# Sheet2.net
KiCad netlist of a schematic drawn in Altium Designer
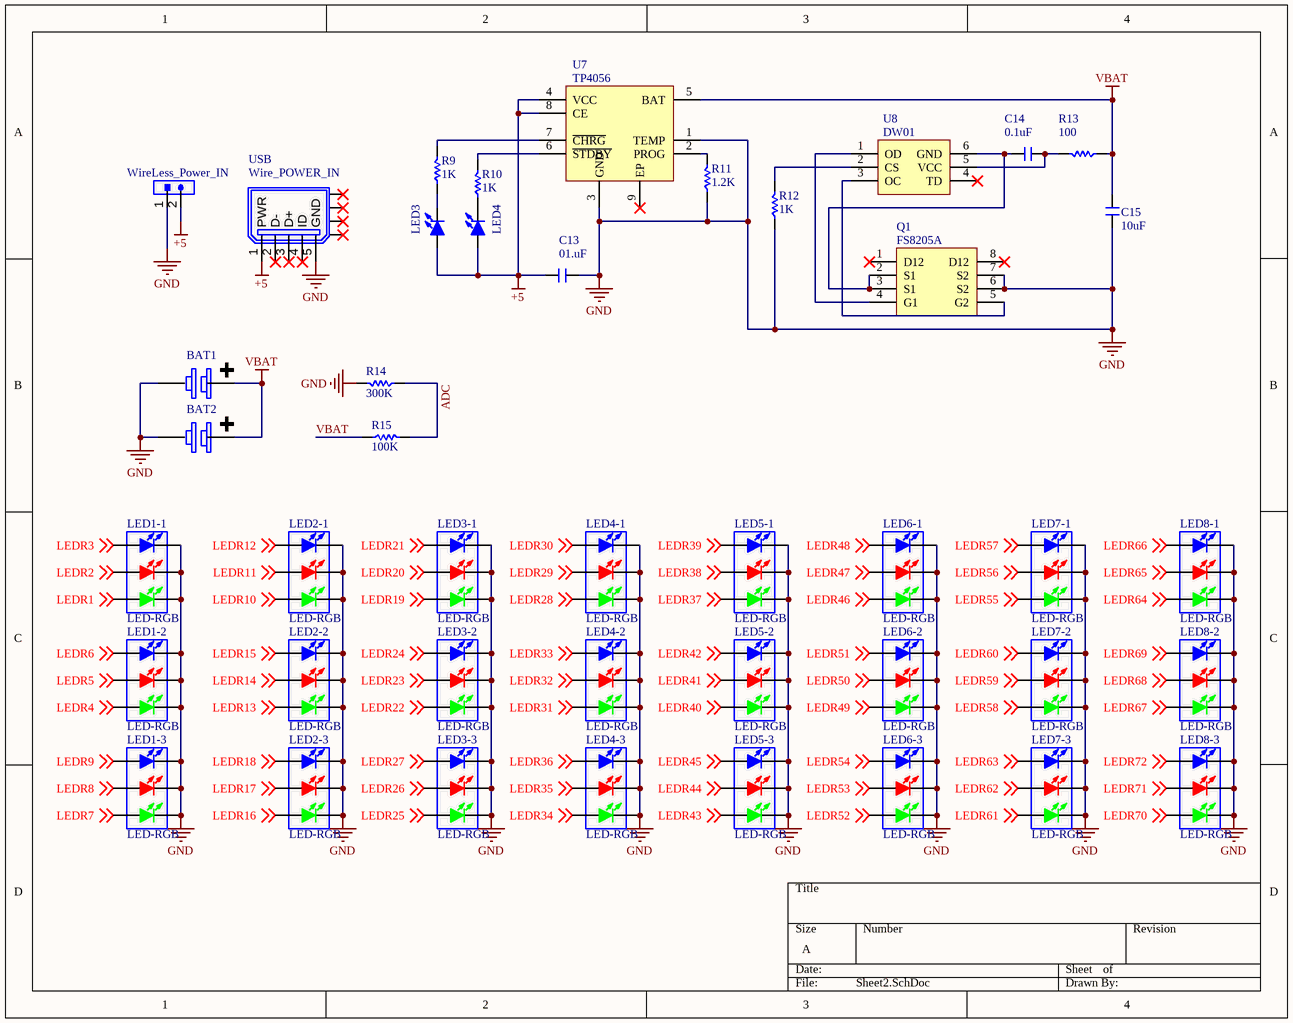
[diagram p0: Sheet2.SchDoc]

(export (version "E")
  (design (tool "Eeschema 10.0.6"))
  (components
    (comp (ref "BAT1")
      (value "Battery 1850")
      (footprint "18650 Single")
      (libsource (lib "Battery Holder") (part "Battery 1850"))
    )
    (comp (ref "BAT2")
      (value "Battery 1850")
      (footprint "18650 Single")
      (libsource (lib "Battery Holder") (part "Battery 1850"))
    )
    (comp (ref "C13")
      (value "01.uF")
      (footprint "C 0402")
      (description "Non-polar patch capacitor")
      (fields (field (name "版权归属") "源创客"))
      (libsource (lib "Passive (Resistor-Capacitor-Inductor-Veristor-Ferrite)") (part "C"))
    )
    (comp (ref "C14")
      (value "0.1uF")
      (footprint "C 0402")
      (description "Non-polar patch capacitor")
      (fields (field (name "版权归属") "源创客"))
      (libsource (lib "Passive (Resistor-Capacitor-Inductor-Veristor-Ferrite)") (part "C"))
    )
    (comp (ref "C15")
      (value "10uF")
      (footprint "C 0603")
      (description "Non-polar patch capacitor")
      (fields (field (name "版权归属") "源创客"))
      (libsource (lib "Passive (Resistor-Capacitor-Inductor-Veristor-Ferrite)") (part "C"))
    )
    (comp (ref "LED1-1")
      (value "LED-RGB")
      (footprint "LED 5050")
      (description "Three primary color LED")
      (fields (field (name "版权归属") "源创客"))
      (libsource (lib "LED") (part "LED-RGB"))
    )
    (comp (ref "LED1-2")
      (value "LED-RGB")
      (footprint "LED 5050")
      (description "Three primary color LED")
      (fields (field (name "版权归属") "源创客"))
      (libsource (lib "LED") (part "LED-RGB"))
    )
    (comp (ref "LED1-3")
      (value "LED-RGB")
      (footprint "LED 5050")
      (description "Three primary color LED")
      (fields (field (name "版权归属") "源创客"))
      (libsource (lib "LED") (part "LED-RGB"))
    )
    (comp (ref "LED2-1")
      (value "LED-RGB")
      (footprint "LED 5050")
      (description "Three primary color LED")
      (fields (field (name "版权归属") "源创客"))
      (libsource (lib "LED") (part "LED-RGB"))
    )
    (comp (ref "LED2-2")
      (value "LED-RGB")
      (footprint "LED 5050")
      (description "Three primary color LED")
      (fields (field (name "版权归属") "源创客"))
      (libsource (lib "LED") (part "LED-RGB"))
    )
    (comp (ref "LED2-3")
      (value "LED-RGB")
      (footprint "LED 5050")
      (description "Three primary color LED")
      (fields (field (name "版权归属") "源创客"))
      (libsource (lib "LED") (part "LED-RGB"))
    )
    (comp (ref "LED3")
      (value "LED-SMD")
      (footprint "LED 0805R")
      (description "Patch LED")
      (fields (field (name "版权归属") "源创客"))
      (libsource (lib "LED") (part "LED-SMD"))
    )
    (comp (ref "LED3-1")
      (value "LED-RGB")
      (footprint "LED 5050")
      (description "Three primary color LED")
      (fields (field (name "版权归属") "源创客"))
      (libsource (lib "LED") (part "LED-RGB"))
    )
    (comp (ref "LED3-2")
      (value "LED-RGB")
      (footprint "LED 5050")
      (description "Three primary color LED")
      (fields (field (name "版权归属") "源创客"))
      (libsource (lib "LED") (part "LED-RGB"))
    )
    (comp (ref "LED3-3")
      (value "LED-RGB")
      (footprint "LED 5050")
      (description "Three primary color LED")
      (fields (field (name "版权归属") "源创客"))
      (libsource (lib "LED") (part "LED-RGB"))
    )
    (comp (ref "LED4")
      (value "LED-SMD")
      (footprint "LED 0805G")
      (description "Patch LED")
      (fields (field (name "版权归属") "源创客"))
      (libsource (lib "LED") (part "LED-SMD"))
    )
    (comp (ref "LED4-1")
      (value "LED-RGB")
      (footprint "LED 5050")
      (description "Three primary color LED")
      (fields (field (name "版权归属") "源创客"))
      (libsource (lib "LED") (part "LED-RGB"))
    )
    (comp (ref "LED4-2")
      (value "LED-RGB")
      (footprint "LED 5050")
      (description "Three primary color LED")
      (fields (field (name "版权归属") "源创客"))
      (libsource (lib "LED") (part "LED-RGB"))
    )
    (comp (ref "LED4-3")
      (value "LED-RGB")
      (footprint "LED 5050")
      (description "Three primary color LED")
      (fields (field (name "版权归属") "源创客"))
      (libsource (lib "LED") (part "LED-RGB"))
    )
    (comp (ref "LED5-1")
      (value "LED-RGB")
      (footprint "LED 5050")
      (description "Three primary color LED")
      (fields (field (name "版权归属") "源创客"))
      (libsource (lib "LED") (part "LED-RGB"))
    )
    (comp (ref "LED5-2")
      (value "LED-RGB")
      (footprint "LED 5050")
      (description "Three primary color LED")
      (fields (field (name "版权归属") "源创客"))
      (libsource (lib "LED") (part "LED-RGB"))
    )
    (comp (ref "LED5-3")
      (value "LED-RGB")
      (footprint "LED 5050")
      (description "Three primary color LED")
      (fields (field (name "版权归属") "源创客"))
      (libsource (lib "LED") (part "LED-RGB"))
    )
    (comp (ref "LED6-1")
      (value "LED-RGB")
      (footprint "LED 5050")
      (description "Three primary color LED")
      (fields (field (name "版权归属") "源创客"))
      (libsource (lib "LED") (part "LED-RGB"))
    )
    (comp (ref "LED6-2")
      (value "LED-RGB")
      (footprint "LED 5050")
      (description "Three primary color LED")
      (fields (field (name "版权归属") "源创客"))
      (libsource (lib "LED") (part "LED-RGB"))
    )
    (comp (ref "LED6-3")
      (value "LED-RGB")
      (footprint "LED 5050")
      (description "Three primary color LED")
      (fields (field (name "版权归属") "源创客"))
      (libsource (lib "LED") (part "LED-RGB"))
    )
    (comp (ref "LED7-1")
      (value "LED-RGB")
      (footprint "LED 5050")
      (description "Three primary color LED")
      (fields (field (name "版权归属") "源创客"))
      (libsource (lib "LED") (part "LED-RGB"))
    )
    (comp (ref "LED7-2")
      (value "LED-RGB")
      (footprint "LED 5050")
      (description "Three primary color LED")
      (fields (field (name "版权归属") "源创客"))
      (libsource (lib "LED") (part "LED-RGB"))
    )
    (comp (ref "LED7-3")
      (value "LED-RGB")
      (footprint "LED 5050")
      (description "Three primary color LED")
      (fields (field (name "版权归属") "源创客"))
      (libsource (lib "LED") (part "LED-RGB"))
    )
    (comp (ref "LED8-1")
      (value "LED-RGB")
      (footprint "LED 5050")
      (description "Three primary color LED")
      (fields (field (name "版权归属") "源创客"))
      (libsource (lib "LED") (part "LED-RGB"))
    )
    (comp (ref "LED8-2")
      (value "LED-RGB")
      (footprint "LED 5050")
      (description "Three primary color LED")
      (fields (field (name "版权归属") "源创客"))
      (libsource (lib "LED") (part "LED-RGB"))
    )
    (comp (ref "LED8-3")
      (value "LED-RGB")
      (footprint "LED 5050")
      (description "Three primary color LED")
      (fields (field (name "版权归属") "源创客"))
      (libsource (lib "LED") (part "LED-RGB"))
    )
    (comp (ref "Q1")
      (value "FS8205A")
      (footprint "SSOP8_L")
      (description "Dual N-Channel Enhancement Mode Power MOSFET")
      (libsource (lib "Integrated Circuit") (part "FS8205A"))
    )
    (comp (ref "R9")
      (value "1K")
      (footprint "R 0402")
      (description "Chip resistor")
      (fields (field (name "版权归属") "源创客"))
      (libsource (lib "Passive (Resistor-Capacitor-Inductor-Veristor-Ferrite)") (part "R"))
    )
    (comp (ref "R10")
      (value "1K")
      (footprint "R 0402")
      (description "Chip resistor")
      (fields (field (name "版权归属") "源创客"))
      (libsource (lib "Passive (Resistor-Capacitor-Inductor-Veristor-Ferrite)") (part "R"))
    )
    (comp (ref "R11")
      (value "1.2K")
      (footprint "R 0402")
      (description "Chip resistor")
      (fields (field (name "版权归属") "源创客"))
      (libsource (lib "Passive (Resistor-Capacitor-Inductor-Veristor-Ferrite)") (part "R"))
    )
    (comp (ref "R12")
      (value "1K")
      (footprint "R 0402")
      (description "Chip resistor")
      (fields (field (name "版权归属") "源创客"))
      (libsource (lib "Passive (Resistor-Capacitor-Inductor-Veristor-Ferrite)") (part "R"))
    )
    (comp (ref "R13")
      (value "100")
      (footprint "R 0402")
      (description "Chip resistor")
      (fields (field (name "版权归属") "源创客"))
      (libsource (lib "Passive (Resistor-Capacitor-Inductor-Veristor-Ferrite)") (part "R"))
    )
    (comp (ref "R14")
      (value "300K")
      (footprint "R 0805")
      (description "Chip resistor")
      (fields (field (name "版权归属") "源创客"))
      (libsource (lib "Passive (Resistor-Capacitor-Inductor-Veristor-Ferrite)") (part "R"))
    )
    (comp (ref "R15")
      (value "100K")
      (footprint "R 0805")
      (description "Chip resistor")
      (fields (field (name "版权归属") "源创客"))
      (libsource (lib "Passive (Resistor-Capacitor-Inductor-Veristor-Ferrite)") (part "R"))
    )
    (comp (ref "U7")
      (value "TP4056")
      (footprint "SOP8_M-EP")
      (description "Lithium battery charge management")
      (fields (field (name "版权归属") "源创客"))
      (libsource (lib "Integrated Circuit") (part "TP4056"))
    )
    (comp (ref "U8")
      (value "DW01")
      (footprint "SOT23-6M")
      (description "Lithium battery overcurrent protection IC")
      (fields (field (name "版权归属") "源创客"))
      (libsource (lib "Integrated Circuit") (part "DW01"))
    )
    (comp (ref "USB")
      (value "Wire_POWER_IN")
      (footprint "USB-micro_B")
      (description "Micro & Mini USB female")
      (fields (field (name "版权归属") "源创客"))
      (libsource (lib "IO (Power-USB-Serial-VGA-RJ-Audio-Buzzer)") (part "USB-5P"))
    )
    (comp (ref "WireLess_Power_IN")
      (value "HDR-1X2")
      (footprint "XH2.54-2P")
      (description "2P Connector")
      (fields (field (name "版权归属") "源创客"))
      (libsource (lib "Connectors") (part "Header 2"))
    )
  )
  (nets
    (net (code "1") (name "+5") (class "Default")
      (node (ref "C13") (pin "2") (pinfunction "2_2") (pintype "passive"))
      (node (ref "LED3") (pin "1") (pinfunction "A_1") (pintype "passive"))
      (node (ref "LED4") (pin "1") (pinfunction "A_1") (pintype "passive"))
      (node (ref "U7") (pin "4") (pinfunction "VCC_4") (pintype "passive"))
      (node (ref "U7") (pin "8") (pinfunction "CE_8") (pintype "passive"))
      (node (ref "USB") (pin "1") (pinfunction "PWR_1") (pintype "power_in"))
      (node (ref "WireLess_Power_IN") (pin "2") (pintype "passive"))
    )
    (net (code "2") (name "/ADC") (class "Default")
      (node (ref "R14") (pin "1") (pinfunction "1_1") (pintype "passive"))
      (node (ref "R15") (pin "2") (pinfunction "2_2") (pintype "passive"))
    )
    (net (code "3") (name "GND") (class "Default")
      (node (ref "BAT1") (pin "2") (pinfunction "-_2") (pintype "passive"))
      (node (ref "BAT2") (pin "2") (pinfunction "-_2") (pintype "passive"))
      (node (ref "C13") (pin "1") (pinfunction "1_1") (pintype "passive"))
      (node (ref "C15") (pin "1") (pinfunction "1_1") (pintype "passive"))
      (node (ref "LED1-1") (pin "2") (pinfunction "BULE_K_2") (pintype "passive"))
      (node (ref "LED1-1") (pin "4") (pinfunction "RED_K_4") (pintype "passive"))
      (node (ref "LED1-1") (pin "6") (pinfunction "GREEN_K_6") (pintype "passive"))
      (node (ref "LED1-2") (pin "2") (pinfunction "BULE_K_2") (pintype "passive"))
      (node (ref "LED1-2") (pin "4") (pinfunction "RED_K_4") (pintype "passive"))
      (node (ref "LED1-2") (pin "6") (pinfunction "GREEN_K_6") (pintype "passive"))
      (node (ref "LED1-3") (pin "2") (pinfunction "BULE_K_2") (pintype "passive"))
      (node (ref "LED1-3") (pin "4") (pinfunction "RED_K_4") (pintype "passive"))
      (node (ref "LED1-3") (pin "6") (pinfunction "GREEN_K_6") (pintype "passive"))
      (node (ref "LED2-1") (pin "2") (pinfunction "BULE_K_2") (pintype "passive"))
      (node (ref "LED2-1") (pin "4") (pinfunction "RED_K_4") (pintype "passive"))
      (node (ref "LED2-1") (pin "6") (pinfunction "GREEN_K_6") (pintype "passive"))
      (node (ref "LED2-2") (pin "2") (pinfunction "BULE_K_2") (pintype "passive"))
      (node (ref "LED2-2") (pin "4") (pinfunction "RED_K_4") (pintype "passive"))
      (node (ref "LED2-2") (pin "6") (pinfunction "GREEN_K_6") (pintype "passive"))
      (node (ref "LED2-3") (pin "2") (pinfunction "BULE_K_2") (pintype "passive"))
      (node (ref "LED2-3") (pin "4") (pinfunction "RED_K_4") (pintype "passive"))
      (node (ref "LED2-3") (pin "6") (pinfunction "GREEN_K_6") (pintype "passive"))
      (node (ref "LED3-1") (pin "2") (pinfunction "BULE_K_2") (pintype "passive"))
      (node (ref "LED3-1") (pin "4") (pinfunction "RED_K_4") (pintype "passive"))
      (node (ref "LED3-1") (pin "6") (pinfunction "GREEN_K_6") (pintype "passive"))
      (node (ref "LED3-2") (pin "2") (pinfunction "BULE_K_2") (pintype "passive"))
      (node (ref "LED3-2") (pin "4") (pinfunction "RED_K_4") (pintype "passive"))
      (node (ref "LED3-2") (pin "6") (pinfunction "GREEN_K_6") (pintype "passive"))
      (node (ref "LED3-3") (pin "2") (pinfunction "BULE_K_2") (pintype "passive"))
      (node (ref "LED3-3") (pin "4") (pinfunction "RED_K_4") (pintype "passive"))
      (node (ref "LED3-3") (pin "6") (pinfunction "GREEN_K_6") (pintype "passive"))
      (node (ref "LED4-1") (pin "2") (pinfunction "BULE_K_2") (pintype "passive"))
      (node (ref "LED4-1") (pin "4") (pinfunction "RED_K_4") (pintype "passive"))
      (node (ref "LED4-1") (pin "6") (pinfunction "GREEN_K_6") (pintype "passive"))
      (node (ref "LED4-2") (pin "2") (pinfunction "BULE_K_2") (pintype "passive"))
      (node (ref "LED4-2") (pin "4") (pinfunction "RED_K_4") (pintype "passive"))
      (node (ref "LED4-2") (pin "6") (pinfunction "GREEN_K_6") (pintype "passive"))
      (node (ref "LED4-3") (pin "2") (pinfunction "BULE_K_2") (pintype "passive"))
      (node (ref "LED4-3") (pin "4") (pinfunction "RED_K_4") (pintype "passive"))
      (node (ref "LED4-3") (pin "6") (pinfunction "GREEN_K_6") (pintype "passive"))
      (node (ref "LED5-1") (pin "2") (pinfunction "BULE_K_2") (pintype "passive"))
      (node (ref "LED5-1") (pin "4") (pinfunction "RED_K_4") (pintype "passive"))
      (node (ref "LED5-1") (pin "6") (pinfunction "GREEN_K_6") (pintype "passive"))
      (node (ref "LED5-2") (pin "2") (pinfunction "BULE_K_2") (pintype "passive"))
      (node (ref "LED5-2") (pin "4") (pinfunction "RED_K_4") (pintype "passive"))
      (node (ref "LED5-2") (pin "6") (pinfunction "GREEN_K_6") (pintype "passive"))
      (node (ref "LED5-3") (pin "2") (pinfunction "BULE_K_2") (pintype "passive"))
      (node (ref "LED5-3") (pin "4") (pinfunction "RED_K_4") (pintype "passive"))
      (node (ref "LED5-3") (pin "6") (pinfunction "GREEN_K_6") (pintype "passive"))
      (node (ref "LED6-1") (pin "2") (pinfunction "BULE_K_2") (pintype "passive"))
      (node (ref "LED6-1") (pin "4") (pinfunction "RED_K_4") (pintype "passive"))
      (node (ref "LED6-1") (pin "6") (pinfunction "GREEN_K_6") (pintype "passive"))
      (node (ref "LED6-2") (pin "2") (pinfunction "BULE_K_2") (pintype "passive"))
      (node (ref "LED6-2") (pin "4") (pinfunction "RED_K_4") (pintype "passive"))
      (node (ref "LED6-2") (pin "6") (pinfunction "GREEN_K_6") (pintype "passive"))
      (node (ref "LED6-3") (pin "2") (pinfunction "BULE_K_2") (pintype "passive"))
      (node (ref "LED6-3") (pin "4") (pinfunction "RED_K_4") (pintype "passive"))
      (node (ref "LED6-3") (pin "6") (pinfunction "GREEN_K_6") (pintype "passive"))
      (node (ref "LED7-1") (pin "2") (pinfunction "BULE_K_2") (pintype "passive"))
      (node (ref "LED7-1") (pin "4") (pinfunction "RED_K_4") (pintype "passive"))
      (node (ref "LED7-1") (pin "6") (pinfunction "GREEN_K_6") (pintype "passive"))
      (node (ref "LED7-2") (pin "2") (pinfunction "BULE_K_2") (pintype "passive"))
      (node (ref "LED7-2") (pin "4") (pinfunction "RED_K_4") (pintype "passive"))
      (node (ref "LED7-2") (pin "6") (pinfunction "GREEN_K_6") (pintype "passive"))
      (node (ref "LED7-3") (pin "2") (pinfunction "BULE_K_2") (pintype "passive"))
      (node (ref "LED7-3") (pin "4") (pinfunction "RED_K_4") (pintype "passive"))
      (node (ref "LED7-3") (pin "6") (pinfunction "GREEN_K_6") (pintype "passive"))
      (node (ref "LED8-1") (pin "2") (pinfunction "BULE_K_2") (pintype "passive"))
      (node (ref "LED8-1") (pin "4") (pinfunction "RED_K_4") (pintype "passive"))
      (node (ref "LED8-1") (pin "6") (pinfunction "GREEN_K_6") (pintype "passive"))
      (node (ref "LED8-2") (pin "2") (pinfunction "BULE_K_2") (pintype "passive"))
      (node (ref "LED8-2") (pin "4") (pinfunction "RED_K_4") (pintype "passive"))
      (node (ref "LED8-2") (pin "6") (pinfunction "GREEN_K_6") (pintype "passive"))
      (node (ref "LED8-3") (pin "2") (pinfunction "BULE_K_2") (pintype "passive"))
      (node (ref "LED8-3") (pin "4") (pinfunction "RED_K_4") (pintype "passive"))
      (node (ref "LED8-3") (pin "6") (pinfunction "GREEN_K_6") (pintype "passive"))
      (node (ref "Q1") (pin "6") (pinfunction "S2_6") (pintype "passive"))
      (node (ref "Q1") (pin "7") (pinfunction "S2_7") (pintype "passive"))
      (node (ref "R11") (pin "1") (pinfunction "1_1") (pintype "passive"))
      (node (ref "R12") (pin "1") (pinfunction "1_1") (pintype "passive"))
      (node (ref "R14") (pin "2") (pinfunction "2_2") (pintype "passive"))
      (node (ref "U7") (pin "1") (pinfunction "TEMP_1") (pintype "passive"))
      (node (ref "U7") (pin "3") (pinfunction "GND_3") (pintype "passive"))
      (node (ref "USB") (pin "5") (pinfunction "GND_5") (pintype "power_in"))
      (node (ref "WireLess_Power_IN") (pin "1") (pintype "passive"))
    )
    (net (code "4") (name "LEDR1") (class "Default")
      (node (ref "LED1-1") (pin "5") (pinfunction "GREEN_A_5") (pintype "passive"))
    )
    (net (code "5") (name "LEDR2") (class "Default")
      (node (ref "LED1-1") (pin "3") (pinfunction "RED_A_3") (pintype "passive"))
    )
    (net (code "6") (name "LEDR3") (class "Default")
      (node (ref "LED1-1") (pin "1") (pinfunction "BULE_A_1") (pintype "passive"))
    )
    (net (code "7") (name "LEDR4") (class "Default")
      (node (ref "LED1-2") (pin "5") (pinfunction "GREEN_A_5") (pintype "passive"))
    )
    (net (code "8") (name "LEDR5") (class "Default")
      (node (ref "LED1-2") (pin "3") (pinfunction "RED_A_3") (pintype "passive"))
    )
    (net (code "9") (name "LEDR6") (class "Default")
      (node (ref "LED1-2") (pin "1") (pinfunction "BULE_A_1") (pintype "passive"))
    )
    (net (code "10") (name "LEDR7") (class "Default")
      (node (ref "LED1-3") (pin "5") (pinfunction "GREEN_A_5") (pintype "passive"))
    )
    (net (code "11") (name "LEDR8") (class "Default")
      (node (ref "LED1-3") (pin "3") (pinfunction "RED_A_3") (pintype "passive"))
    )
    (net (code "12") (name "LEDR9") (class "Default")
      (node (ref "LED1-3") (pin "1") (pinfunction "BULE_A_1") (pintype "passive"))
    )
    (net (code "13") (name "LEDR10") (class "Default")
      (node (ref "LED2-1") (pin "5") (pinfunction "GREEN_A_5") (pintype "passive"))
    )
    (net (code "14") (name "LEDR11") (class "Default")
      (node (ref "LED2-1") (pin "3") (pinfunction "RED_A_3") (pintype "passive"))
    )
    (net (code "15") (name "LEDR12") (class "Default")
      (node (ref "LED2-1") (pin "1") (pinfunction "BULE_A_1") (pintype "passive"))
    )
    (net (code "16") (name "LEDR13") (class "Default")
      (node (ref "LED2-2") (pin "5") (pinfunction "GREEN_A_5") (pintype "passive"))
    )
    (net (code "17") (name "LEDR14") (class "Default")
      (node (ref "LED2-2") (pin "3") (pinfunction "RED_A_3") (pintype "passive"))
    )
    (net (code "18") (name "LEDR15") (class "Default")
      (node (ref "LED2-2") (pin "1") (pinfunction "BULE_A_1") (pintype "passive"))
    )
    (net (code "19") (name "LEDR16") (class "Default")
      (node (ref "LED2-3") (pin "5") (pinfunction "GREEN_A_5") (pintype "passive"))
    )
    (net (code "20") (name "LEDR17") (class "Default")
      (node (ref "LED2-3") (pin "3") (pinfunction "RED_A_3") (pintype "passive"))
    )
    (net (code "21") (name "LEDR18") (class "Default")
      (node (ref "LED2-3") (pin "1") (pinfunction "BULE_A_1") (pintype "passive"))
    )
    (net (code "22") (name "LEDR19") (class "Default")
      (node (ref "LED3-1") (pin "5") (pinfunction "GREEN_A_5") (pintype "passive"))
    )
    (net (code "23") (name "LEDR20") (class "Default")
      (node (ref "LED3-1") (pin "3") (pinfunction "RED_A_3") (pintype "passive"))
    )
    (net (code "24") (name "LEDR21") (class "Default")
      (node (ref "LED3-1") (pin "1") (pinfunction "BULE_A_1") (pintype "passive"))
    )
    (net (code "25") (name "LEDR22") (class "Default")
      (node (ref "LED3-2") (pin "5") (pinfunction "GREEN_A_5") (pintype "passive"))
    )
    (net (code "26") (name "LEDR23") (class "Default")
      (node (ref "LED3-2") (pin "3") (pinfunction "RED_A_3") (pintype "passive"))
    )
    (net (code "27") (name "LEDR24") (class "Default")
      (node (ref "LED3-2") (pin "1") (pinfunction "BULE_A_1") (pintype "passive"))
    )
    (net (code "28") (name "LEDR25") (class "Default")
      (node (ref "LED3-3") (pin "5") (pinfunction "GREEN_A_5") (pintype "passive"))
    )
    (net (code "29") (name "LEDR26") (class "Default")
      (node (ref "LED3-3") (pin "3") (pinfunction "RED_A_3") (pintype "passive"))
    )
    (net (code "30") (name "LEDR27") (class "Default")
      (node (ref "LED3-3") (pin "1") (pinfunction "BULE_A_1") (pintype "passive"))
    )
    (net (code "31") (name "LEDR28") (class "Default")
      (node (ref "LED4-1") (pin "5") (pinfunction "GREEN_A_5") (pintype "passive"))
    )
    (net (code "32") (name "LEDR29") (class "Default")
      (node (ref "LED4-1") (pin "3") (pinfunction "RED_A_3") (pintype "passive"))
    )
    (net (code "33") (name "LEDR30") (class "Default")
      (node (ref "LED4-1") (pin "1") (pinfunction "BULE_A_1") (pintype "passive"))
    )
    (net (code "34") (name "LEDR31") (class "Default")
      (node (ref "LED4-2") (pin "5") (pinfunction "GREEN_A_5") (pintype "passive"))
    )
    (net (code "35") (name "LEDR32") (class "Default")
      (node (ref "LED4-2") (pin "3") (pinfunction "RED_A_3") (pintype "passive"))
    )
    (net (code "36") (name "LEDR33") (class "Default")
      (node (ref "LED4-2") (pin "1") (pinfunction "BULE_A_1") (pintype "passive"))
    )
    (net (code "37") (name "LEDR34") (class "Default")
      (node (ref "LED4-3") (pin "5") (pinfunction "GREEN_A_5") (pintype "passive"))
    )
    (net (code "38") (name "LEDR35") (class "Default")
      (node (ref "LED4-3") (pin "3") (pinfunction "RED_A_3") (pintype "passive"))
    )
    (net (code "39") (name "LEDR36") (class "Default")
      (node (ref "LED4-3") (pin "1") (pinfunction "BULE_A_1") (pintype "passive"))
    )
    (net (code "40") (name "LEDR37") (class "Default")
      (node (ref "LED5-1") (pin "5") (pinfunction "GREEN_A_5") (pintype "passive"))
    )
    (net (code "41") (name "LEDR38") (class "Default")
      (node (ref "LED5-1") (pin "3") (pinfunction "RED_A_3") (pintype "passive"))
    )
    (net (code "42") (name "LEDR39") (class "Default")
      (node (ref "LED5-1") (pin "1") (pinfunction "BULE_A_1") (pintype "passive"))
    )
    (net (code "43") (name "LEDR40") (class "Default")
      (node (ref "LED5-2") (pin "5") (pinfunction "GREEN_A_5") (pintype "passive"))
    )
    (net (code "44") (name "LEDR41") (class "Default")
      (node (ref "LED5-2") (pin "3") (pinfunction "RED_A_3") (pintype "passive"))
    )
    (net (code "45") (name "LEDR42") (class "Default")
      (node (ref "LED5-2") (pin "1") (pinfunction "BULE_A_1") (pintype "passive"))
    )
    (net (code "46") (name "LEDR43") (class "Default")
      (node (ref "LED5-3") (pin "5") (pinfunction "GREEN_A_5") (pintype "passive"))
    )
    (net (code "47") (name "LEDR44") (class "Default")
      (node (ref "LED5-3") (pin "3") (pinfunction "RED_A_3") (pintype "passive"))
    )
    (net (code "48") (name "LEDR45") (class "Default")
      (node (ref "LED5-3") (pin "1") (pinfunction "BULE_A_1") (pintype "passive"))
    )
    (net (code "49") (name "LEDR46") (class "Default")
      (node (ref "LED6-1") (pin "5") (pinfunction "GREEN_A_5") (pintype "passive"))
    )
    (net (code "50") (name "LEDR47") (class "Default")
      (node (ref "LED6-1") (pin "3") (pinfunction "RED_A_3") (pintype "passive"))
    )
    (net (code "51") (name "LEDR48") (class "Default")
      (node (ref "LED6-1") (pin "1") (pinfunction "BULE_A_1") (pintype "passive"))
    )
    (net (code "52") (name "LEDR49") (class "Default")
      (node (ref "LED6-2") (pin "5") (pinfunction "GREEN_A_5") (pintype "passive"))
    )
    (net (code "53") (name "LEDR50") (class "Default")
      (node (ref "LED6-2") (pin "3") (pinfunction "RED_A_3") (pintype "passive"))
    )
    (net (code "54") (name "LEDR51") (class "Default")
      (node (ref "LED6-2") (pin "1") (pinfunction "BULE_A_1") (pintype "passive"))
    )
    (net (code "55") (name "LEDR52") (class "Default")
      (node (ref "LED6-3") (pin "5") (pinfunction "GREEN_A_5") (pintype "passive"))
    )
    (net (code "56") (name "LEDR53") (class "Default")
      (node (ref "LED6-3") (pin "3") (pinfunction "RED_A_3") (pintype "passive"))
    )
    (net (code "57") (name "LEDR54") (class "Default")
      (node (ref "LED6-3") (pin "1") (pinfunction "BULE_A_1") (pintype "passive"))
    )
    (net (code "58") (name "LEDR55") (class "Default")
      (node (ref "LED7-1") (pin "5") (pinfunction "GREEN_A_5") (pintype "passive"))
    )
    (net (code "59") (name "LEDR56") (class "Default")
      (node (ref "LED7-1") (pin "3") (pinfunction "RED_A_3") (pintype "passive"))
    )
    (net (code "60") (name "LEDR57") (class "Default")
      (node (ref "LED7-1") (pin "1") (pinfunction "BULE_A_1") (pintype "passive"))
    )
    (net (code "61") (name "LEDR58") (class "Default")
      (node (ref "LED7-2") (pin "5") (pinfunction "GREEN_A_5") (pintype "passive"))
    )
    (net (code "62") (name "LEDR59") (class "Default")
      (node (ref "LED7-2") (pin "3") (pinfunction "RED_A_3") (pintype "passive"))
    )
    (net (code "63") (name "LEDR60") (class "Default")
      (node (ref "LED7-2") (pin "1") (pinfunction "BULE_A_1") (pintype "passive"))
    )
    (net (code "64") (name "LEDR61") (class "Default")
      (node (ref "LED7-3") (pin "5") (pinfunction "GREEN_A_5") (pintype "passive"))
    )
    (net (code "65") (name "LEDR62") (class "Default")
      (node (ref "LED7-3") (pin "3") (pinfunction "RED_A_3") (pintype "passive"))
    )
    (net (code "66") (name "LEDR63") (class "Default")
      (node (ref "LED7-3") (pin "1") (pinfunction "BULE_A_1") (pintype "passive"))
    )
    (net (code "67") (name "LEDR64") (class "Default")
      (node (ref "LED8-1") (pin "5") (pinfunction "GREEN_A_5") (pintype "passive"))
    )
    (net (code "68") (name "LEDR65") (class "Default")
      (node (ref "LED8-1") (pin "3") (pinfunction "RED_A_3") (pintype "passive"))
    )
    (net (code "69") (name "LEDR66") (class "Default")
      (node (ref "LED8-1") (pin "1") (pinfunction "BULE_A_1") (pintype "passive"))
    )
    (net (code "70") (name "LEDR67") (class "Default")
      (node (ref "LED8-2") (pin "5") (pinfunction "GREEN_A_5") (pintype "passive"))
    )
    (net (code "71") (name "LEDR68") (class "Default")
      (node (ref "LED8-2") (pin "3") (pinfunction "RED_A_3") (pintype "passive"))
    )
    (net (code "72") (name "LEDR69") (class "Default")
      (node (ref "LED8-2") (pin "1") (pinfunction "BULE_A_1") (pintype "passive"))
    )
    (net (code "73") (name "LEDR70") (class "Default")
      (node (ref "LED8-3") (pin "5") (pinfunction "GREEN_A_5") (pintype "passive"))
    )
    (net (code "74") (name "LEDR71") (class "Default")
      (node (ref "LED8-3") (pin "3") (pinfunction "RED_A_3") (pintype "passive"))
    )
    (net (code "75") (name "LEDR72") (class "Default")
      (node (ref "LED8-3") (pin "1") (pinfunction "BULE_A_1") (pintype "passive"))
    )
    (net (code "76") (name "Net-(LED3-K)") (class "Default")
      (node (ref "LED3") (pin "2") (pinfunction "K_2") (pintype "passive"))
      (node (ref "R9") (pin "1") (pinfunction "1_1") (pintype "passive"))
    )
    (net (code "77") (name "Net-(LED4-K)") (class "Default")
      (node (ref "LED4") (pin "2") (pinfunction "K_2") (pintype "passive"))
      (node (ref "R10") (pin "1") (pinfunction "1_1") (pintype "passive"))
    )
    (net (code "78") (name "Net-(Q1-G1)") (class "Default")
      (node (ref "Q1") (pin "4") (pinfunction "G1_4") (pintype "passive"))
      (node (ref "U8") (pin "1") (pinfunction "OD_1") (pintype "passive"))
    )
    (net (code "79") (name "Net-(Q1-G2)") (class "Default")
      (node (ref "Q1") (pin "5") (pinfunction "G2_5") (pintype "passive"))
      (node (ref "U8") (pin "3") (pinfunction "OC_3") (pintype "passive"))
    )
    (net (code "80") (name "Net-(U7-PROG)") (class "Default")
      (node (ref "R11") (pin "2") (pinfunction "2_2") (pintype "passive"))
      (node (ref "U7") (pin "2") (pinfunction "PROG_2") (pintype "passive"))
    )
    (net (code "81") (name "Net-(U7-~{CHRG})") (class "Default")
      (node (ref "R9") (pin "2") (pinfunction "2_2") (pintype "passive"))
      (node (ref "U7") (pin "7") (pinfunction "~{CHRG}_7") (pintype "passive"))
    )
    (net (code "82") (name "Net-(U7-~{STDBY})") (class "Default")
      (node (ref "R10") (pin "2") (pinfunction "2_2") (pintype "passive"))
      (node (ref "U7") (pin "6") (pinfunction "~{STDBY}_6") (pintype "passive"))
    )
    (net (code "83") (name "Net-(U8-CS)") (class "Default")
      (node (ref "R12") (pin "2") (pinfunction "2_2") (pintype "passive"))
      (node (ref "U8") (pin "2") (pinfunction "CS_2") (pintype "passive"))
    )
    (net (code "84") (name "Net-(U8-GND)") (class "Default")
      (node (ref "C14") (pin "1") (pinfunction "1_1") (pintype "passive"))
      (node (ref "Q1") (pin "2") (pinfunction "S1_2") (pintype "passive"))
      (node (ref "Q1") (pin "3") (pinfunction "S1_3") (pintype "passive"))
      (node (ref "U8") (pin "6") (pinfunction "GND_6") (pintype "passive"))
    )
    (net (code "85") (name "Net-(U8-VCC)") (class "Default")
      (node (ref "C14") (pin "2") (pinfunction "2_2") (pintype "passive"))
      (node (ref "R13") (pin "2") (pinfunction "2_2") (pintype "passive"))
      (node (ref "U8") (pin "5") (pinfunction "VCC_5") (pintype "passive"))
    )
    (net (code "86") (name "VBAT") (class "Default")
      (node (ref "BAT1") (pin "1") (pinfunction "+_1") (pintype "passive"))
      (node (ref "BAT2") (pin "1") (pinfunction "+_1") (pintype "passive"))
      (node (ref "C15") (pin "2") (pinfunction "2_2") (pintype "passive"))
      (node (ref "R13") (pin "1") (pinfunction "1_1") (pintype "passive"))
      (node (ref "R15") (pin "1") (pinfunction "1_1") (pintype "passive"))
      (node (ref "U7") (pin "5") (pinfunction "BAT_5") (pintype "passive"))
    )
    (net (code "87") (name "unconnected-(Q1-D12-Pad1)") (class "Default")
      (node (ref "Q1") (pin "1") (pinfunction "D12_1") (pintype "passive+no_connect"))
    )
    (net (code "88") (name "unconnected-(Q1-D12-Pad8)") (class "Default")
      (node (ref "Q1") (pin "8") (pinfunction "D12_8") (pintype "passive+no_connect"))
    )
    (net (code "89") (name "unconnected-(U7-EP-Pad9)") (class "Default")
      (node (ref "U7") (pin "9") (pinfunction "EP_9") (pintype "passive+no_connect"))
    )
    (net (code "90") (name "unconnected-(U8-TD-Pad4)") (class "Default")
      (node (ref "U8") (pin "4") (pinfunction "TD_4") (pintype "passive+no_connect"))
    )
    (net (code "91") (name "unconnected-(USB-D+-Pad3)") (class "Default")
      (node (ref "USB") (pin "3") (pinfunction "D+_3") (pintype "tri_state+no_connect"))
    )
    (net (code "92") (name "unconnected-(USB-D--Pad2)") (class "Default")
      (node (ref "USB") (pin "2") (pinfunction "D-_2") (pintype "tri_state+no_connect"))
    )
    (net (code "93") (name "unconnected-(USB-ID-Pad4)") (class "Default")
      (node (ref "USB") (pin "4") (pinfunction "ID_4") (pintype "passive+no_connect"))
    )
    (net (code "94") (name "unconnected-(USB-SHIELD-Pad5)") (class "Default")
      (node (ref "USB") (pin "5") (pinfunction "SHIELD_5") (pintype "passive+no_connect"))
    )
    (net (code "95") (name "unconnected-(USB-SHIELD-Pad5)_1") (class "Default")
      (node (ref "USB") (pin "5") (pinfunction "SHIELD_5") (pintype "passive+no_connect"))
    )
    (net (code "96") (name "unconnected-(USB-SHIELD-Pad5)_2") (class "Default")
      (node (ref "USB") (pin "5") (pinfunction "SHIELD_5") (pintype "passive+no_connect"))
    )
    (net (code "97") (name "unconnected-(USB-SHIELD-Pad5)_3") (class "Default")
      (node (ref "USB") (pin "5") (pinfunction "SHIELD_5") (pintype "passive+no_connect"))
    )
  )
)
